# half_bridge.net
KiCad netlist of a schematic drawn in Altium Designer
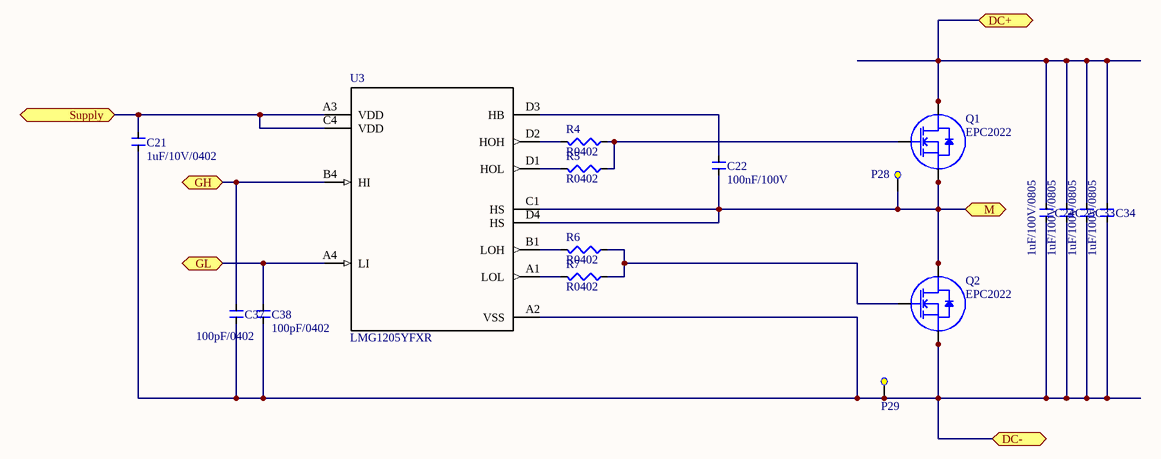
[diagram p0: half_bridge.SchDoc]

(export (version "E")
  (design (tool "Eeschema 10.0.6"))
  (components
    (comp (ref "C21")
      (value "1uF/10V/0402/X5R/10%")
      (footprint "C0402_FOR_DRIVER")
      (description "311-1439-1-ND")
      (fields (field (name "ALTIUM_UNNAMED_1") "1uF/10V/0402"))
      (libsource (lib "Maohang_Qiu_Lib") (part "1uF/10V/0402/X5R/10%"))
    )
    (comp (ref "C22")
      (value "100nF/100V/0402/X5R/10%")
      (footprint "C0402_FOR_DRIVER")
      (description "GRM155R62A104KE14D")
      (fields (field (name "ALTIUM_UNNAMED_1") "100nF/100V"))
      (libsource (lib "Maohang_Qiu_Lib") (part "100nF/100V/0402/X5R/10%"))
    )
    (comp (ref "C24")
      (value "1uF/100V/20%/0805/X7S")
      (footprint "C0805")
      (description "445-5206-1-ND")
      (fields (field (name "ALTIUM_UNNAMED_1") "1uF/100V/0805"))
      (libsource (lib "Maohang_Qiu_Lib") (part "1uF/100V/20%/0805/X7S"))
    )
    (comp (ref "C25")
      (value "1uF/100V/20%/0805/X7S")
      (footprint "C0805")
      (description "445-5206-1-ND")
      (fields (field (name "ALTIUM_UNNAMED_1") "1uF/100V/0805"))
      (libsource (lib "Maohang_Qiu_Lib") (part "1uF/100V/20%/0805/X7S"))
    )
    (comp (ref "C33")
      (value "1uF/100V/20%/0805/X7S")
      (footprint "C0805")
      (description "445-5206-1-ND")
      (fields (field (name "ALTIUM_UNNAMED_1") "1uF/100V/0805"))
      (libsource (lib "Maohang_Qiu_Lib") (part "1uF/100V/20%/0805/X7S"))
    )
    (comp (ref "C34")
      (value "1uF/100V/20%/0805/X7S")
      (footprint "C0805")
      (description "445-5206-1-ND")
      (fields (field (name "ALTIUM_UNNAMED_1") "1uF/100V/0805"))
      (libsource (lib "Maohang_Qiu_Lib") (part "1uF/100V/20%/0805/X7S"))
    )
    (comp (ref "C37")
      (value "100pF/50V/5%/0402/C0G")
      (footprint "C0402_FOR_DRIVER")
      (description "311-1024-1-ND")
      (fields (field (name "ALTIUM_UNNAMED_1") "100pF/0402"))
      (libsource (lib "Maohang_Qiu_Lib") (part "100pF/50V/5%/0402/C0G"))
    )
    (comp (ref "C38")
      (value "100pF/50V/5%/0402/C0G")
      (footprint "C0402_FOR_DRIVER")
      (description "311-1024-1-ND")
      (fields (field (name "ALTIUM_UNNAMED_1") "100pF/0402"))
      (libsource (lib "Maohang_Qiu_Lib") (part "100pF/50V/5%/0402/C0G"))
    )
    (comp (ref "P28")
      (value "Test_Point_0.5mm")
      (footprint "Test_Point-0.5mm")
      (libsource (lib "Maohang_Qiu_Lib") (part "Test_Point_0.5mm"))
    )
    (comp (ref "P29")
      (value "Test_Point_0.5mm")
      (footprint "Test_Point-0.5mm")
      (libsource (lib "Maohang_Qiu_Lib") (part "Test_Point_0.5mm"))
    )
    (comp (ref "Q1")
      (value "EPC2022")
      (footprint "EPC2x40XL")
      (description "100V 60A 3.2mE")
      (fields (field (name "MFG") "EPC"))
      (libsource (lib "EPC_2018Q2") (part "EPC2022"))
    )
    (comp (ref "Q2")
      (value "EPC2022")
      (footprint "EPC2x40XL")
      (description "100V 60A 3.2mE")
      (fields (field (name "MFG") "EPC"))
      (libsource (lib "EPC_2018Q2") (part "EPC2022"))
    )
    (comp (ref "R4")
      (value "R0402")
      (footprint "R0402_FOR_DRIVER")
      (description "Resistor")
      (libsource (lib "Maohang_Qiu_Lib") (part "R0402"))
    )
    (comp (ref "R5")
      (value "R0402")
      (footprint "R0402_FOR_DRIVER")
      (description "Resistor")
      (libsource (lib "Maohang_Qiu_Lib") (part "R0402"))
    )
    (comp (ref "R6")
      (value "R0402")
      (footprint "R0402_FOR_DRIVER")
      (description "Resistor")
      (libsource (lib "Maohang_Qiu_Lib") (part "R0402"))
    )
    (comp (ref "R7")
      (value "R0402")
      (footprint "R0402_FOR_DRIVER")
      (description "Resistor")
      (libsource (lib "Maohang_Qiu_Lib") (part "R0402"))
    )
    (comp (ref "U3")
      (value "LMG1205YFXR")
      (footprint "YFX0012AHAP")
      (description "No Description Available")
      (fields
        (field (name "MANUFACTURER") "Texas Instruments")
        (field (name "COPYRIGHT") "Copyright (C) 2018 Accelerated Designs. All rights reserved")
      )
      (libsource (lib "Maohang_Qiu_Device_Library") (part "LMG1205YFXR"))
    )
  )
  (nets
    (net (code "1") (name "/DC+") (class "Default")
      (node (ref "C24") (pin "2") (pinfunction "2_2") (pintype "passive"))
      (node (ref "C25") (pin "2") (pinfunction "2_2") (pintype "passive"))
      (node (ref "C33") (pin "2") (pinfunction "2_2") (pintype "passive"))
      (node (ref "C34") (pin "2") (pinfunction "2_2") (pintype "passive"))
      (node (ref "Q1") (pin "11") (pinfunction "D5_11") (pintype "open_collector"))
      (node (ref "Q1") (pin "12") (pinfunction "D6_12") (pintype "open_collector"))
      (node (ref "Q1") (pin "15") (pinfunction "D7_15") (pintype "open_collector"))
      (node (ref "Q1") (pin "16") (pinfunction "D8_16") (pintype "open_collector"))
      (node (ref "Q1") (pin "19") (pinfunction "D9_19") (pintype "open_collector"))
      (node (ref "Q1") (pin "20") (pinfunction "D10_20") (pintype "open_collector"))
      (node (ref "Q1") (pin "23") (pinfunction "D11_23") (pintype "open_collector"))
      (node (ref "Q1") (pin "24") (pinfunction "D12_24") (pintype "open_collector"))
      (node (ref "Q1") (pin "27") (pinfunction "D13_27") (pintype "open_collector"))
      (node (ref "Q1") (pin "28") (pinfunction "D14_28") (pintype "open_collector"))
      (node (ref "Q1") (pin "3") (pinfunction "D1_3") (pintype "open_collector"))
      (node (ref "Q1") (pin "4") (pinfunction "D2_4") (pintype "open_collector"))
      (node (ref "Q1") (pin "7") (pinfunction "D3_7") (pintype "open_collector"))
      (node (ref "Q1") (pin "8") (pinfunction "D4_8") (pintype "open_collector"))
    )
    (net (code "2") (name "/DC-") (class "Default")
      (node (ref "C21") (pin "1") (pinfunction "1_1") (pintype "passive"))
      (node (ref "C24") (pin "1") (pinfunction "1_1") (pintype "passive"))
      (node (ref "C25") (pin "1") (pinfunction "1_1") (pintype "passive"))
      (node (ref "C33") (pin "1") (pinfunction "1_1") (pintype "passive"))
      (node (ref "C34") (pin "1") (pinfunction "1_1") (pintype "passive"))
      (node (ref "C37") (pin "1") (pinfunction "1_1") (pintype "passive"))
      (node (ref "C38") (pin "1") (pinfunction "1_1") (pintype "passive"))
      (node (ref "P29") (pin "1") (pinfunction "Pri1+_1") (pintype "passive"))
      (node (ref "Q2") (pin "10") (pinfunction "S5_10") (pintype "open_emitter"))
      (node (ref "Q2") (pin "13") (pinfunction "S6_13") (pintype "open_emitter"))
      (node (ref "Q2") (pin "14") (pinfunction "S7_14") (pintype "open_emitter"))
      (node (ref "Q2") (pin "17") (pinfunction "S8_17") (pintype "open_emitter"))
      (node (ref "Q2") (pin "18") (pinfunction "S9_18") (pintype "open_emitter"))
      (node (ref "Q2") (pin "2") (pinfunction "S1_2") (pintype "open_emitter"))
      (node (ref "Q2") (pin "21") (pinfunction "S10_21") (pintype "open_emitter"))
      (node (ref "Q2") (pin "22") (pinfunction "S11_22") (pintype "open_emitter"))
      (node (ref "Q2") (pin "25") (pinfunction "S12_25") (pintype "open_emitter"))
      (node (ref "Q2") (pin "26") (pinfunction "S13_26") (pintype "open_emitter"))
      (node (ref "Q2") (pin "29") (pinfunction "S14_29") (pintype "open_emitter"))
      (node (ref "Q2") (pin "30") (pinfunction "Sub_30") (pintype "open_emitter"))
      (node (ref "Q2") (pin "5") (pinfunction "S2_5") (pintype "open_emitter"))
      (node (ref "Q2") (pin "6") (pinfunction "S3_6") (pintype "open_emitter"))
      (node (ref "Q2") (pin "9") (pinfunction "S4_9") (pintype "open_emitter"))
      (node (ref "U3") (pin "A2") (pinfunction "VSS_A2") (pintype "power_in"))
    )
    (net (code "3") (name "/GH") (class "Default")
      (node (ref "C37") (pin "2") (pinfunction "2_2") (pintype "passive"))
      (node (ref "U3") (pin "B4") (pinfunction "HI_B4") (pintype "input"))
    )
    (net (code "4") (name "/GL") (class "Default")
      (node (ref "C38") (pin "2") (pinfunction "2_2") (pintype "passive"))
      (node (ref "U3") (pin "A4") (pinfunction "LI_A4") (pintype "input"))
    )
    (net (code "5") (name "/M") (class "Default")
      (node (ref "C22") (pin "1") (pinfunction "1_1") (pintype "passive"))
      (node (ref "P28") (pin "1") (pinfunction "Pri1+_1") (pintype "passive"))
      (node (ref "Q1") (pin "10") (pinfunction "S5_10") (pintype "open_emitter"))
      (node (ref "Q1") (pin "13") (pinfunction "S6_13") (pintype "open_emitter"))
      (node (ref "Q1") (pin "14") (pinfunction "S7_14") (pintype "open_emitter"))
      (node (ref "Q1") (pin "17") (pinfunction "S8_17") (pintype "open_emitter"))
      (node (ref "Q1") (pin "18") (pinfunction "S9_18") (pintype "open_emitter"))
      (node (ref "Q1") (pin "2") (pinfunction "S1_2") (pintype "open_emitter"))
      (node (ref "Q1") (pin "21") (pinfunction "S10_21") (pintype "open_emitter"))
      (node (ref "Q1") (pin "22") (pinfunction "S11_22") (pintype "open_emitter"))
      (node (ref "Q1") (pin "25") (pinfunction "S12_25") (pintype "open_emitter"))
      (node (ref "Q1") (pin "26") (pinfunction "S13_26") (pintype "open_emitter"))
      (node (ref "Q1") (pin "29") (pinfunction "S14_29") (pintype "open_emitter"))
      (node (ref "Q1") (pin "30") (pinfunction "Sub_30") (pintype "open_emitter"))
      (node (ref "Q1") (pin "5") (pinfunction "S2_5") (pintype "open_emitter"))
      (node (ref "Q1") (pin "6") (pinfunction "S3_6") (pintype "open_emitter"))
      (node (ref "Q1") (pin "9") (pinfunction "S4_9") (pintype "open_emitter"))
      (node (ref "Q2") (pin "11") (pinfunction "D5_11") (pintype "open_collector"))
      (node (ref "Q2") (pin "12") (pinfunction "D6_12") (pintype "open_collector"))
      (node (ref "Q2") (pin "15") (pinfunction "D7_15") (pintype "open_collector"))
      (node (ref "Q2") (pin "16") (pinfunction "D8_16") (pintype "open_collector"))
      (node (ref "Q2") (pin "19") (pinfunction "D9_19") (pintype "open_collector"))
      (node (ref "Q2") (pin "20") (pinfunction "D10_20") (pintype "open_collector"))
      (node (ref "Q2") (pin "23") (pinfunction "D11_23") (pintype "open_collector"))
      (node (ref "Q2") (pin "24") (pinfunction "D12_24") (pintype "open_collector"))
      (node (ref "Q2") (pin "27") (pinfunction "D13_27") (pintype "open_collector"))
      (node (ref "Q2") (pin "28") (pinfunction "D14_28") (pintype "open_collector"))
      (node (ref "Q2") (pin "3") (pinfunction "D1_3") (pintype "open_collector"))
      (node (ref "Q2") (pin "4") (pinfunction "D2_4") (pintype "open_collector"))
      (node (ref "Q2") (pin "7") (pinfunction "D3_7") (pintype "open_collector"))
      (node (ref "Q2") (pin "8") (pinfunction "D4_8") (pintype "open_collector"))
      (node (ref "U3") (pin "C1") (pinfunction "HS_C1") (pintype "power_in"))
      (node (ref "U3") (pin "D4") (pinfunction "HS_D4") (pintype "power_in"))
    )
    (net (code "6") (name "/Supply") (class "Default")
      (node (ref "C21") (pin "2") (pinfunction "2_2") (pintype "passive"))
      (node (ref "U3") (pin "A3") (pinfunction "VDD_A3") (pintype "power_in"))
      (node (ref "U3") (pin "C4") (pinfunction "VDD_C4") (pintype "power_in"))
    )
    (net (code "7") (name "Net-(Q1-G)") (class "Default")
      (node (ref "Q1") (pin "1") (pinfunction "G_1") (pintype "passive"))
      (node (ref "R4") (pin "2") (pinfunction "2_2") (pintype "passive"))
      (node (ref "R5") (pin "2") (pinfunction "2_2") (pintype "passive"))
    )
    (net (code "8") (name "Net-(Q2-G)") (class "Default")
      (node (ref "Q2") (pin "1") (pinfunction "G_1") (pintype "passive"))
      (node (ref "R6") (pin "2") (pinfunction "2_2") (pintype "passive"))
      (node (ref "R7") (pin "2") (pinfunction "2_2") (pintype "passive"))
    )
    (net (code "9") (name "Net-(U3-HB)") (class "Default")
      (node (ref "C22") (pin "2") (pinfunction "2_2") (pintype "passive"))
      (node (ref "U3") (pin "D3") (pinfunction "HB_D3") (pintype "power_in"))
    )
    (net (code "10") (name "Net-(U3-HOH)") (class "Default")
      (node (ref "R4") (pin "1") (pinfunction "1_1") (pintype "passive"))
      (node (ref "U3") (pin "D2") (pinfunction "HOH_D2") (pintype "output"))
    )
    (net (code "11") (name "Net-(U3-HOL)") (class "Default")
      (node (ref "R5") (pin "1") (pinfunction "1_1") (pintype "passive"))
      (node (ref "U3") (pin "D1") (pinfunction "HOL_D1") (pintype "output"))
    )
    (net (code "12") (name "Net-(U3-LOH)") (class "Default")
      (node (ref "R6") (pin "1") (pinfunction "1_1") (pintype "passive"))
      (node (ref "U3") (pin "B1") (pinfunction "LOH_B1") (pintype "output"))
    )
    (net (code "13") (name "Net-(U3-LOL)") (class "Default")
      (node (ref "R7") (pin "1") (pinfunction "1_1") (pintype "passive"))
      (node (ref "U3") (pin "A1") (pinfunction "LOL_A1") (pintype "output"))
    )
  )
)
